# trace_6.net
KiCad netlist of a schematic drawn in Altium Designer
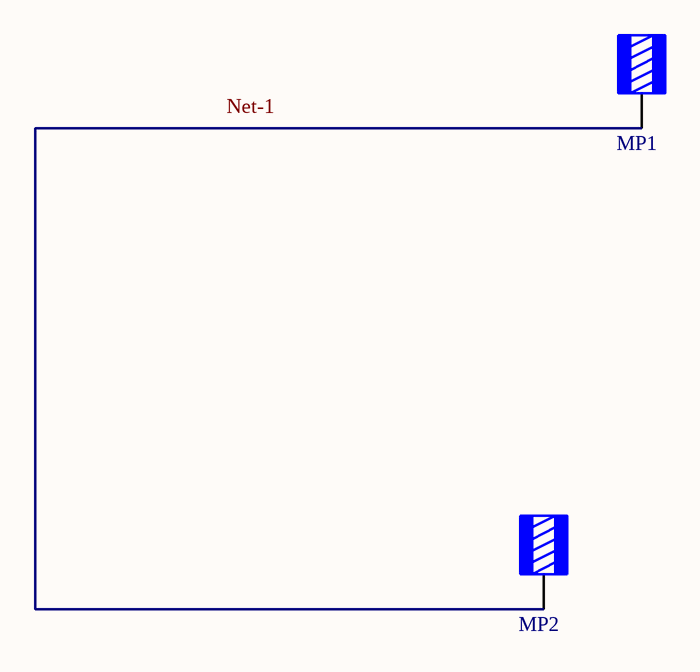
[diagram p0: trace_6.SchDoc]

(export (version "E")
  (design (tool "Eeschema 10.0.6"))
  (components
    (comp (ref "MP1")
      (value "74651194R")
      (footprint "WURTH 74651194")
      (description "TERM REDCUBE 9PIN PCB")
      (fields (field (name "MANUFACTURER") "Würth Elektronik"))
      (libsource (lib "Celestial Altium Library - altium_library") (part "MOUNTING POINT"))
    )
    (comp (ref "MP2")
      (value "74650074R")
      (footprint "WURTH 74650074")
      (description "TERM REDCUBE M4 4PIN PCB")
      (fields (field (name "MANUFACTURER") "Würth Elektronik"))
      (libsource (lib "Celestial Altium Library - altium_library") (part "MOUNTING POINT"))
    )
  )
  (nets
    (net (code "2") (name "Net-(MP1-Pad1)") (class "Default")
      (node (ref "MP1") (pin "1") (pinfunction "1_1") (pintype "passive"))
      (node (ref "MP2") (pin "1") (pinfunction "1_1") (pintype "passive"))
    )
  )
)
